# dimmer.net
KiCad netlist of a schematic drawn in EAGLE
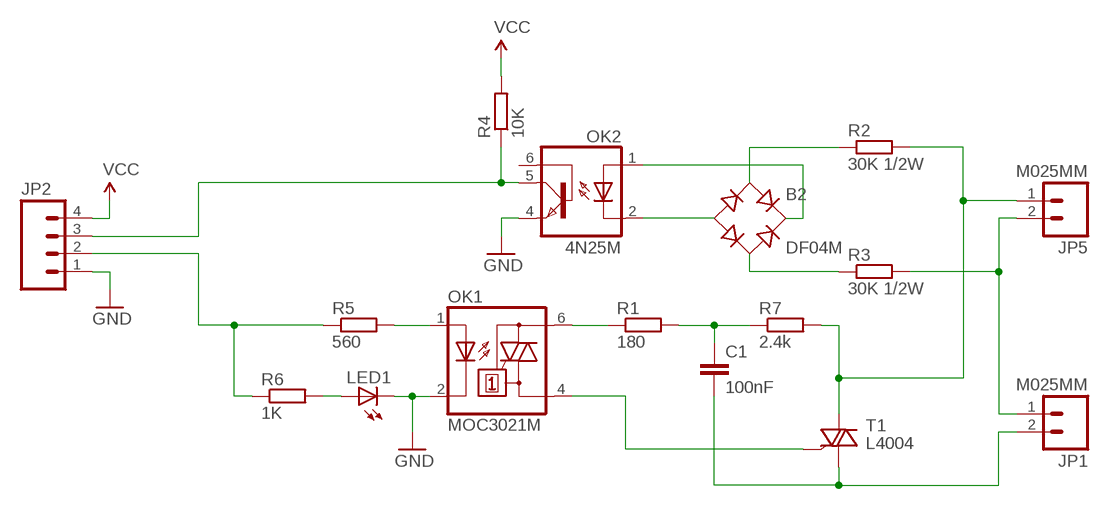
[diagram p0: schematic, sheet 1]

(export (version "E")
  (design (tool "Eeschema 10.0.6"))
  (components
    (comp (ref "B2")
      (value "DF04M")
      (footprint "eagle-import:B-DIL")
      (libsource (lib "eagle-import") (part "B-DIL"))
    )
    (comp (ref "C1")
      (value "100nF")
      (footprint "eagle-import:C050-025X075")
      (libsource (lib "eagle-import") (part "C-EU050-025X075"))
    )
    (comp (ref "JP1")
      (value "M025MM")
      (footprint "eagle-import:SCREWTERMINAL-5MM-2")
      (libsource (lib "eagle-import") (part "M025MM"))
    )
    (comp (ref "JP2")
      (value "M04LOCK")
      (footprint "eagle-import:1X04_LOCK")
      (libsource (lib "eagle-import") (part "M04LOCK"))
    )
    (comp (ref "JP5")
      (value "M025MM")
      (footprint "eagle-import:SCREWTERMINAL-5MM-2")
      (libsource (lib "eagle-import") (part "M025MM"))
    )
    (comp (ref "LED1")
      (value "LED5MM")
      (footprint "eagle-import:LED5MM")
      (libsource (lib "eagle-import") (part "LED5MM"))
    )
    (comp (ref "OK1")
      (value "MOC3021M")
      (footprint "eagle-import:DIL06")
      (fields (field (name "MF") "FAIRCHILD SEMICONDUCTOR") (field (name "MPN") "MOC3021-M"))
      (libsource (lib "eagle-import") (part "MOC30M21"))
    )
    (comp (ref "OK2")
      (value "4N25M")
      (footprint "eagle-import:DIL06")
      (fields (field (name "MPN") "4N25-M"))
      (libsource (lib "eagle-import") (part "4N?M25"))
    )
    (comp (ref "R1")
      (value "180")
      (footprint "eagle-import:0309_12")
      (libsource (lib "eagle-import") (part "R-EU_0309/12"))
    )
    (comp (ref "R2")
      (value "30K 1/2W")
      (footprint "eagle-import:0309_12")
      (libsource (lib "eagle-import") (part "R-EU_0309/12"))
    )
    (comp (ref "R3")
      (value "30K 1/2W")
      (footprint "eagle-import:0309_12")
      (libsource (lib "eagle-import") (part "R-EU_0309/12"))
    )
    (comp (ref "R4")
      (value "10K")
      (footprint "eagle-import:0207_2V")
      (libsource (lib "eagle-import") (part "R-EU_0207/2V"))
    )
    (comp (ref "R5")
      (value "560")
      (footprint "eagle-import:0207_2V")
      (libsource (lib "eagle-import") (part "R-EU_0207/2V"))
    )
    (comp (ref "R6")
      (value "1K")
      (footprint "eagle-import:0207_2V")
      (libsource (lib "eagle-import") (part "R-EU_0207/2V"))
    )
    (comp (ref "R7")
      (value "2.4k")
      (footprint "eagle-import:0309_12")
      (libsource (lib "eagle-import") (part "R-EU_0309/12"))
    )
    (comp (ref "T1")
      (value "L4004")
      (footprint "eagle-import:TO220AB")
      (libsource (lib "eagle-import") (part "BT136"))
    )
  )
  (nets
    (net (code "1") (name "GND") (class "Default")
      (node (ref "JP2") (pin "1") (pinfunction "1_1") (pintype "passive"))
      (node (ref "LED1") (pin "K") (pinfunction "C_K") (pintype "passive"))
      (node (ref "OK1") (pin "2") (pinfunction "C_2") (pintype "passive"))
      (node (ref "OK2") (pin "4") (pinfunction "EMI_4") (pintype "passive"))
    )
    (net (code "2") (name "Net-(B2-PadAC1)") (class "Default")
      (node (ref "B2") (pin "AC1") (pinfunction "AC1_AC1") (pintype "passive"))
      (node (ref "R2") (pin "1") (pinfunction "1_1") (pintype "passive"))
    )
    (net (code "3") (name "Net-(B2-PadAC2)") (class "Default")
      (node (ref "B2") (pin "AC2") (pinfunction "AC2_AC2") (pintype "passive"))
      (node (ref "R3") (pin "1") (pinfunction "1_1") (pintype "passive"))
    )
    (net (code "4") (name "Net-(C1-Pad1)") (class "Default")
      (node (ref "C1") (pin "1") (pinfunction "1_1") (pintype "passive"))
      (node (ref "R1") (pin "2") (pinfunction "2_2") (pintype "passive"))
      (node (ref "R7") (pin "1") (pinfunction "1_1") (pintype "passive"))
    )
    (net (code "5") (name "Net-(JP1-Pad1)") (class "Default")
      (node (ref "JP1") (pin "1") (pinfunction "1_1") (pintype "passive"))
      (node (ref "JP5") (pin "2") (pinfunction "2_2") (pintype "passive"))
      (node (ref "R3") (pin "2") (pinfunction "2_2") (pintype "passive"))
    )
    (net (code "6") (name "Net-(JP2-Pad2)") (class "Default")
      (node (ref "JP2") (pin "2") (pinfunction "2_2") (pintype "passive"))
      (node (ref "R5") (pin "1") (pinfunction "1_1") (pintype "passive"))
      (node (ref "R6") (pin "1") (pinfunction "1_1") (pintype "passive"))
    )
    (net (code "7") (name "Net-(LED1-PadA)") (class "Default")
      (node (ref "LED1") (pin "A") (pinfunction "A_A") (pintype "passive"))
      (node (ref "R6") (pin "2") (pinfunction "2_2") (pintype "passive"))
    )
    (net (code "8") (name "Net-(OK1-A)") (class "Default")
      (node (ref "OK1") (pin "1") (pinfunction "A_1") (pintype "passive"))
      (node (ref "R5") (pin "2") (pinfunction "2_2") (pintype "passive"))
    )
    (net (code "9") (name "Net-(OK1-A1)") (class "Default")
      (node (ref "OK1") (pin "4") (pinfunction "A1_4") (pintype "passive"))
      (node (ref "T1") (pin "3") (pinfunction "G_3") (pintype "passive"))
    )
    (net (code "10") (name "Net-(OK1-A2)") (class "Default")
      (node (ref "OK1") (pin "6") (pinfunction "A2_6") (pintype "passive"))
      (node (ref "R1") (pin "1") (pinfunction "1_1") (pintype "passive"))
    )
    (net (code "11") (name "Net-(OK2-A)") (class "Default")
      (node (ref "B2") (pin "+") (pinfunction "+_+") (pintype "passive"))
      (node (ref "OK2") (pin "1") (pinfunction "A_1") (pintype "passive"))
    )
    (net (code "12") (name "Net-(OK2-C)") (class "Default")
      (node (ref "B2") (pin "-") (pinfunction "-_-") (pintype "passive"))
      (node (ref "OK2") (pin "2") (pinfunction "C_2") (pintype "passive"))
    )
    (net (code "13") (name "Net-(OK2-COL)") (class "Default")
      (node (ref "JP2") (pin "3") (pinfunction "3_3") (pintype "passive"))
      (node (ref "OK2") (pin "5") (pinfunction "COL_5") (pintype "passive"))
      (node (ref "R4") (pin "1") (pinfunction "1_1") (pintype "passive"))
    )
    (net (code "14") (name "Net-(T1-A1)") (class "Default")
      (node (ref "C1") (pin "2") (pinfunction "2_2") (pintype "passive"))
      (node (ref "JP1") (pin "2") (pinfunction "2_2") (pintype "passive"))
      (node (ref "T1") (pin "1") (pinfunction "A1_1") (pintype "passive"))
    )
    (net (code "15") (name "Net-(T1-A2)") (class "Default")
      (node (ref "JP5") (pin "1") (pinfunction "1_1") (pintype "passive"))
      (node (ref "R2") (pin "2") (pinfunction "2_2") (pintype "passive"))
      (node (ref "R7") (pin "2") (pinfunction "2_2") (pintype "passive"))
      (node (ref "T1") (pin "2") (pinfunction "A2_2") (pintype "passive"))
    )
    (net (code "16") (name "VCC") (class "Default")
      (node (ref "JP2") (pin "4") (pinfunction "4_4") (pintype "passive"))
      (node (ref "R4") (pin "2") (pinfunction "2_2") (pintype "passive"))
    )
    (net (code "17") (name "unconnected-(OK2-BAS-Pad6)") (class "Default")
      (node (ref "OK2") (pin "6") (pinfunction "BAS_6") (pintype "passive"))
    )
  )
)
